# PCIe_USB30_Conn_Internal_Vertical.net
KiCad netlist of a schematic drawn in Altium Designer
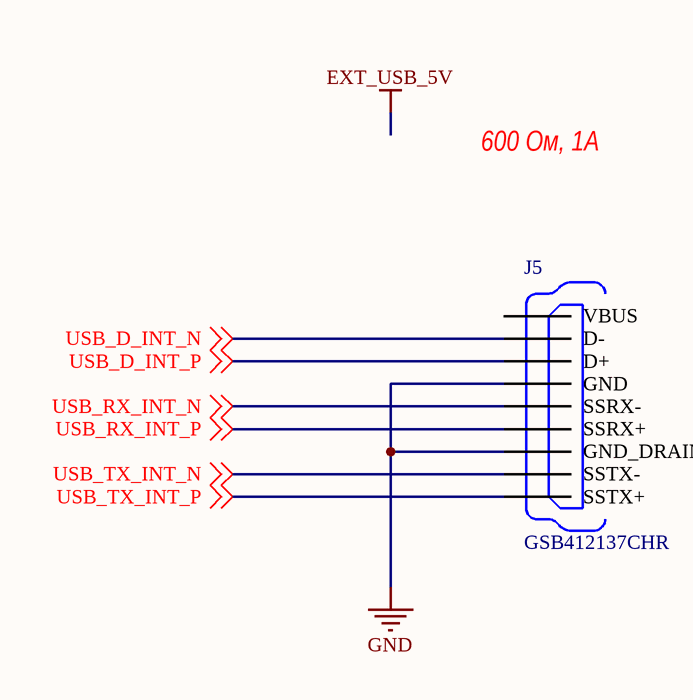
[diagram p0: PCIe_USB30_Conn_Internal_Vertical.SchDoc]

(export (version "E")
  (design (tool "Eeschema 10.0.6"))
  (components
    (comp (ref "J5")
      (value "GSB412137CHR")
      (footprint "AMPHENOL_GSB412137CHR")
      (fields (field (name "DIGI-KEY_PART_NUMBER") "GSB412137CHR-ND") (field (name "MF") "Amphenol ICC"))
      (libsource (lib "GSB412137CHR") (part "GSB412137CHR"))
    )
  )
  (nets
    (net (code "2") (name "GND") (class "Default")
      (node (ref "J5") (pin "4") (pinfunction "GND_4") (pintype "passive"))
      (node (ref "J5") (pin "7") (pinfunction "GND_DRAIN_7") (pintype "passive"))
    )
    (net (code "3") (name "USB_D_INT_N") (class "Default")
      (node (ref "J5") (pin "2") (pinfunction "D-_2") (pintype "passive"))
    )
    (net (code "4") (name "USB_D_INT_P") (class "Default")
      (node (ref "J5") (pin "3") (pinfunction "D+_3") (pintype "passive"))
    )
    (net (code "5") (name "USB_RX_INT_N") (class "Default")
      (node (ref "J5") (pin "5") (pinfunction "SSRX-_5") (pintype "passive"))
    )
    (net (code "6") (name "USB_RX_INT_P") (class "Default")
      (node (ref "J5") (pin "6") (pinfunction "SSRX+_6") (pintype "passive"))
    )
    (net (code "7") (name "USB_TX_INT_N") (class "Default")
      (node (ref "J5") (pin "8") (pinfunction "SSTX-_8") (pintype "passive"))
    )
    (net (code "8") (name "USB_TX_INT_P") (class "Default")
      (node (ref "J5") (pin "9") (pinfunction "SSTX+_9") (pintype "passive"))
    )
    (net (code "9") (name "unconnected-(J5-VBUS-Pad1)") (class "Default")
      (node (ref "J5") (pin "1") (pinfunction "VBUS_1") (pintype "passive"))
    )
  )
)
